# SCH___2025-09-30.net
KiCad netlist of a schematic drawn in EasyEDA
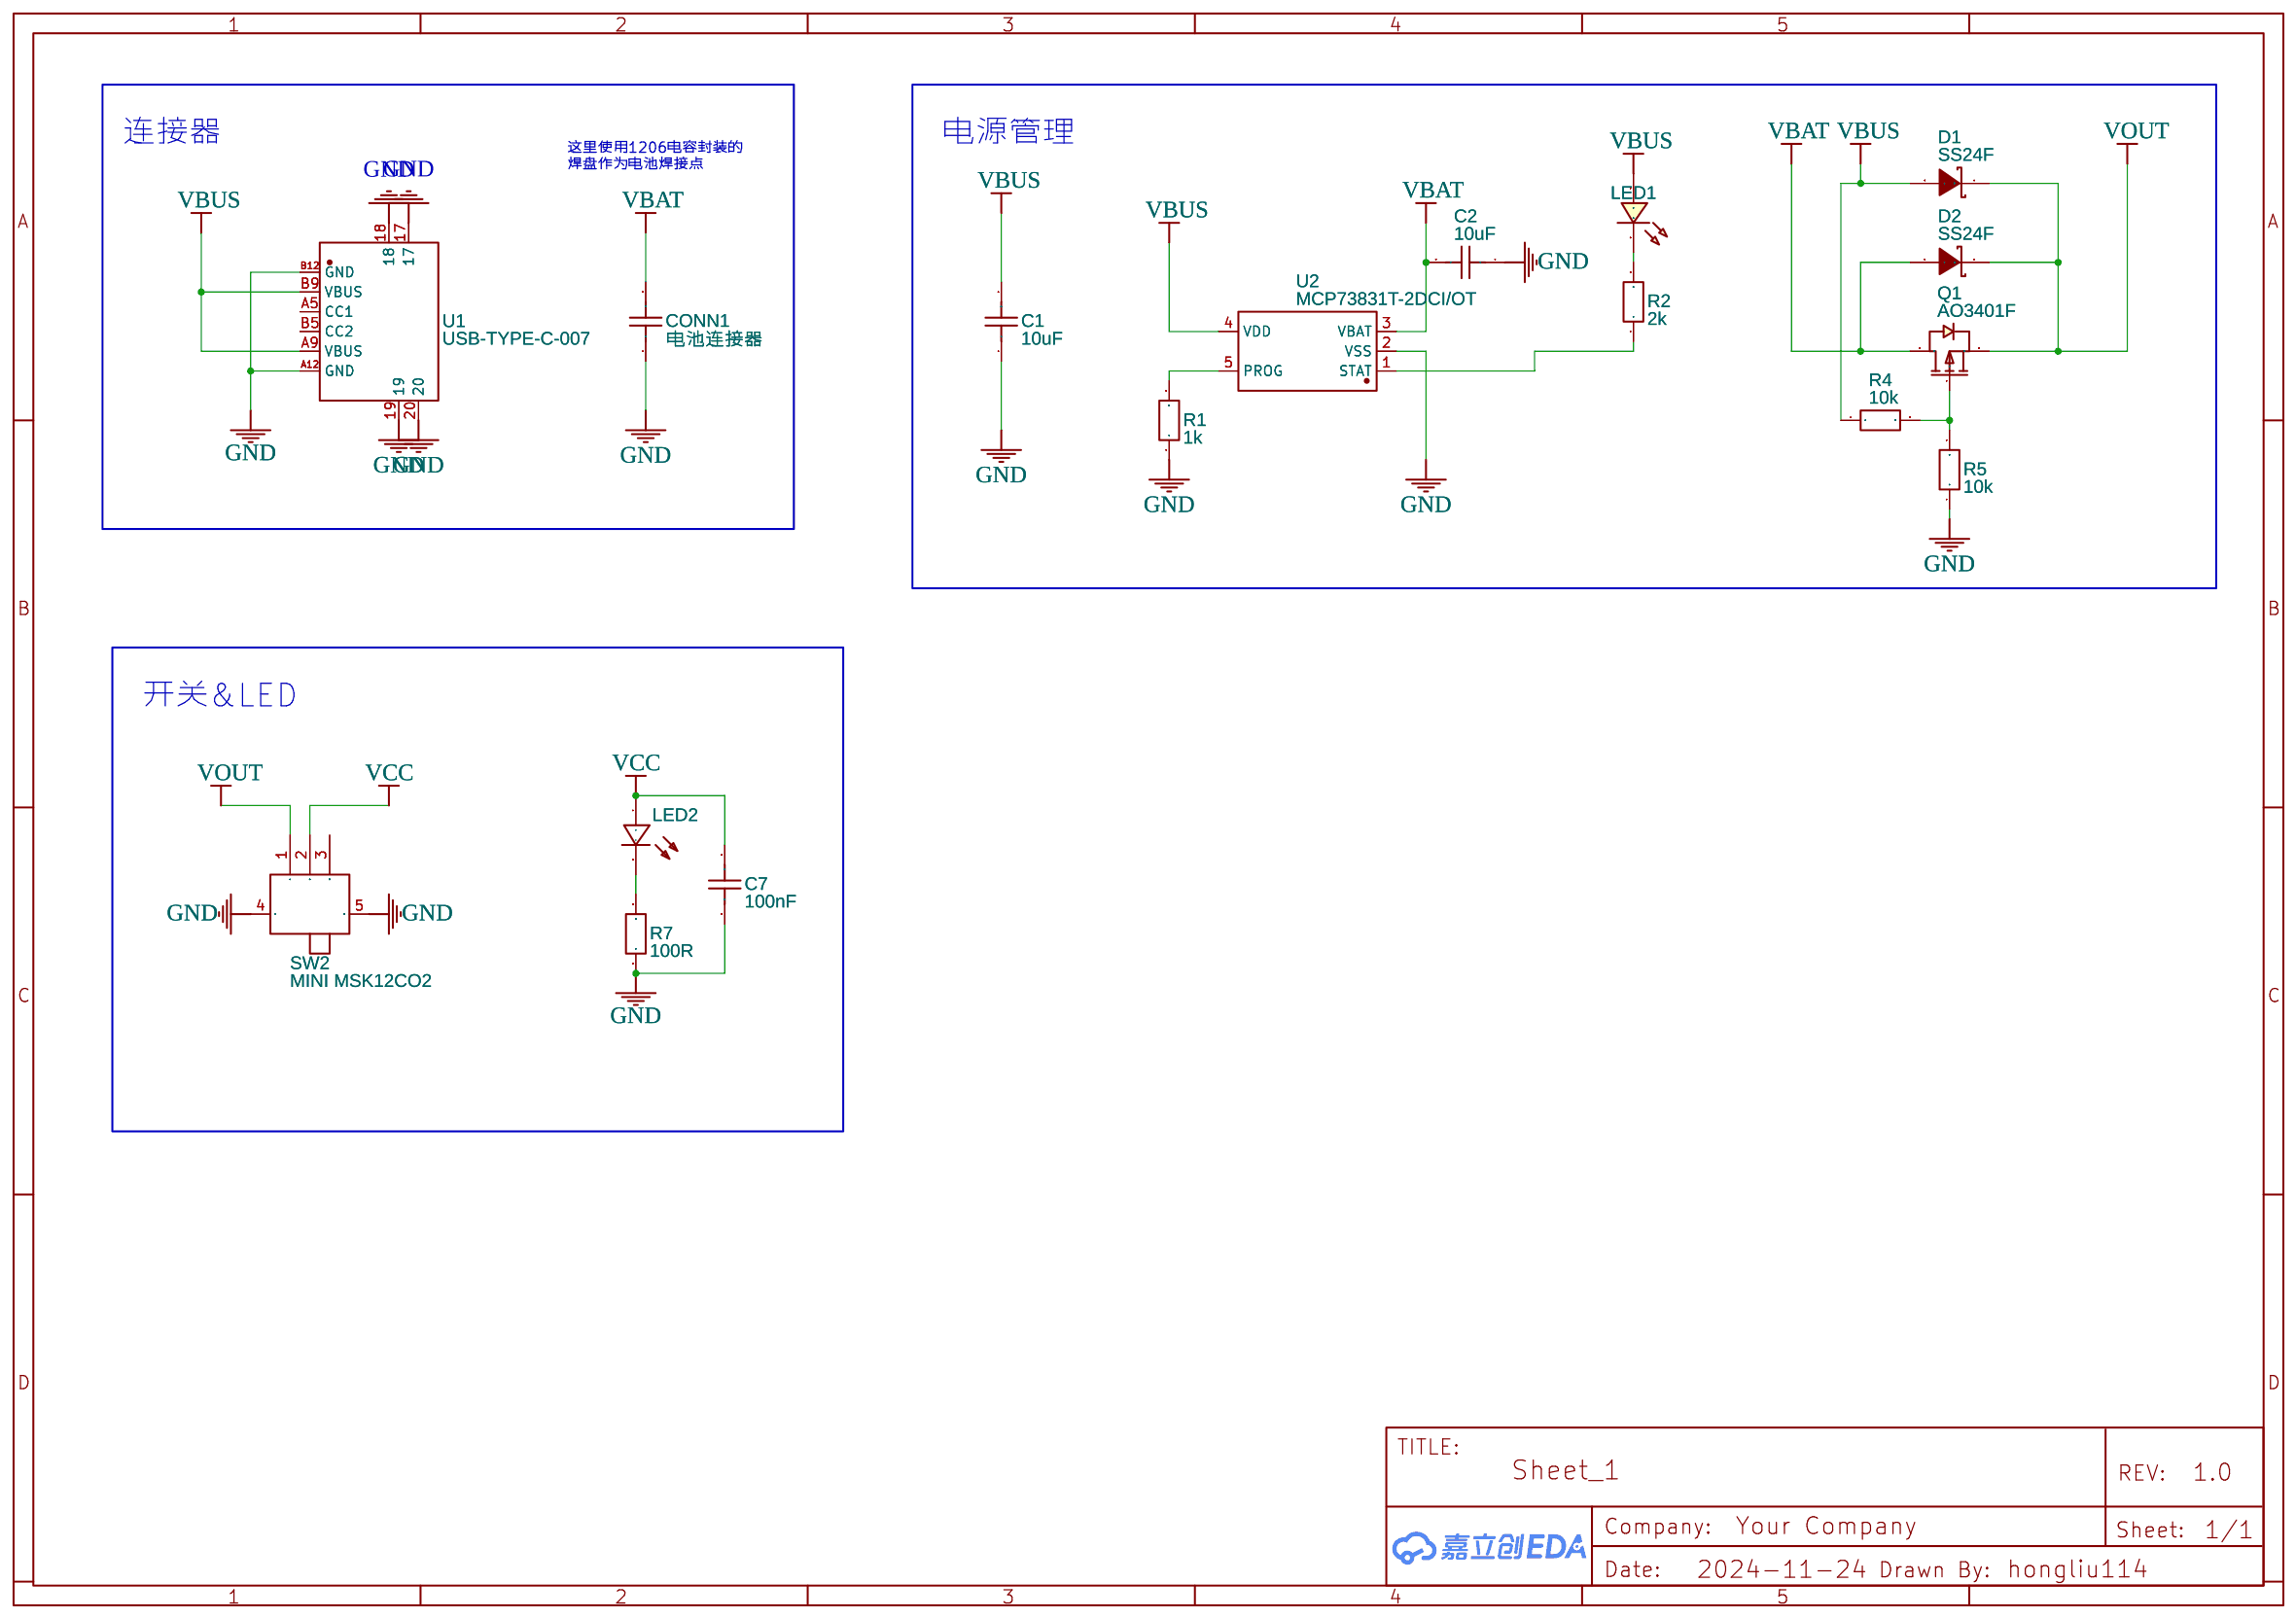
[diagram p0: schematic sheet]

(export (version "E")
  (design (tool "Eeschema 10.0.6"))
  (components
    (comp (ref "C1") (value "10uF") (libsource (lib "") (part "C_0603_US_1")))
    (comp (ref "C2") (value "10uF") (libsource (lib "") (part "C_0603_US")))
    (comp (ref "C7") (value "100nF") (libsource (lib "") (part "C_0603_US_2")))
    (comp (ref "CONN1")
      (value "电池连接器")
      (fields
        (field (name "Manufacturer Part") "C1206X119D8HACAUTO")
        (field (name "Manufacturer") "KEMET(基美)")
      )
      (libsource (lib "") (part "C1206X119D8HACAUTO"))
    )
    (comp (ref "D1")
      (value "SS24F")
      (fields (field (name "Manufacturer") "晶导微电子"))
      (libsource (lib "") (part "SS24F"))
    )
    (comp (ref "D2")
      (value "SS24F")
      (fields (field (name "Manufacturer") "晶导微电子"))
      (libsource (lib "") (part "SS24F"))
    )
    (comp (ref "LED1")
      (value "LED-0603_G")
      (fields
        (field (name "Manufacturer Part") "19-217/R6C-AL1M2VY/3T")
        (field (name "Manufacturer") "EVERLIGHT(台湾亿光)")
      )
      (libsource (lib "") (part "LED-0603_R"))
    )
    (comp (ref "LED2") (value "LED陶瓷灯丝(26MM)") (libsource (lib "") (part "LED陶瓷灯丝(26MM)")))
    (comp (ref "Q1")
      (value "AO3401F")
      (fields (field (name "Manufacturer") "BORN(伯恩半导体)"))
      (libsource (lib "") (part "AO3401F"))
    )
    (comp (ref "R1") (value "1k") (libsource (lib "") (part "R_0603_EU_1")))
    (comp (ref "R2") (value "2k") (libsource (lib "") (part "R_0603_EU_1")))
    (comp (ref "R4") (value "10k") (libsource (lib "") (part "R_0603_EU")))
    (comp (ref "R5") (value "10k") (libsource (lib "") (part "R_0603_EU_1")))
    (comp (ref "R7") (value "100R") (libsource (lib "") (part "R_0603_EU_1")))
    (comp (ref "SW2")
      (value "MINI MSK12CO2")
      (fields (field (name "Manufacturer") "SHOU HAN(首韩)"))
      (libsource (lib "") (part "MINI MSK12CO2"))
    )
    (comp (ref "U1")
      (value "USB-TYPE-C-007")
      (fields (field (name "Manufacturer") "DEALON(德艺隆)"))
      (libsource (lib "") (part "USB-TYPE-C-007"))
    )
    (comp (ref "U2")
      (value "MCP73831T-2DCI/OT")
      (fields (field (name "Manufacturer") "MICROCHIP(美国微芯)"))
      (libsource (lib "") (part "MCP73831T-2DCI/OT"))
    )
  )
  (nets
    (net (code "1") (name "GND") (class "Default")
      (node (ref "C1") (pin "1") (pinfunction "1_1") (pintype "unspecified"))
      (node (ref "C2") (pin "1") (pinfunction "1_1") (pintype "unspecified"))
      (node (ref "C7") (pin "2") (pinfunction "2_2") (pintype "unspecified"))
      (node (ref "CONN1") (pin "1") (pinfunction "1_1") (pintype "unspecified"))
      (node (ref "R1") (pin "1") (pinfunction "1_1") (pintype "unspecified"))
      (node (ref "R5") (pin "1") (pinfunction "1_1") (pintype "unspecified"))
      (node (ref "R7") (pin "1") (pinfunction "1_1") (pintype "unspecified"))
      (node (ref "SW2") (pin "4") (pinfunction "4_4") (pintype "unspecified"))
      (node (ref "SW2") (pin "5") (pinfunction "5_5") (pintype "unspecified"))
      (node (ref "U1") (pin "17") (pinfunction "17_17") (pintype "unspecified"))
      (node (ref "U1") (pin "18") (pinfunction "18_18") (pintype "unspecified"))
      (node (ref "U1") (pin "19") (pinfunction "19_19") (pintype "unspecified"))
      (node (ref "U1") (pin "20") (pinfunction "20_20") (pintype "unspecified"))
      (node (ref "U1") (pin "A12") (pinfunction "GND_A12") (pintype "unspecified"))
      (node (ref "U1") (pin "B12") (pinfunction "GND_B12") (pintype "unspecified"))
      (node (ref "U2") (pin "2") (pinfunction "VSS_2") (pintype "unspecified"))
    )
    (net (code "2") (name "Net-(LED1-Pad2)") (class "Default")
      (node (ref "LED1") (pin "2") (pinfunction "2_2") (pintype "unspecified"))
      (node (ref "R2") (pin "2") (pinfunction "2_2") (pintype "unspecified"))
    )
    (net (code "3") (name "Net-(LED2--)") (class "Default")
      (node (ref "LED2") (pin "2") (pinfunction "-_2") (pintype "unspecified"))
      (node (ref "R7") (pin "2") (pinfunction "2_2") (pintype "unspecified"))
    )
    (net (code "4") (name "Net-(Q1-G)") (class "Default")
      (node (ref "Q1") (pin "1") (pinfunction "G_1") (pintype "unspecified"))
      (node (ref "R4") (pin "2") (pinfunction "2_2") (pintype "unspecified"))
      (node (ref "R5") (pin "2") (pinfunction "2_2") (pintype "unspecified"))
    )
    (net (code "5") (name "Net-(U2-PROG)") (class "Default")
      (node (ref "R1") (pin "2") (pinfunction "2_2") (pintype "unspecified"))
      (node (ref "U2") (pin "5") (pinfunction "PROG_5") (pintype "unspecified"))
    )
    (net (code "6") (name "Net-(U2-STAT)") (class "Default")
      (node (ref "R2") (pin "1") (pinfunction "1_1") (pintype "unspecified"))
      (node (ref "U2") (pin "1") (pinfunction "STAT_1") (pintype "unspecified"))
    )
    (net (code "7") (name "VBAT") (class "Default")
      (node (ref "C2") (pin "2") (pinfunction "2_2") (pintype "unspecified"))
      (node (ref "CONN1") (pin "2") (pinfunction "2_2") (pintype "unspecified"))
      (node (ref "D2") (pin "2") (pinfunction "A_2") (pintype "unspecified"))
      (node (ref "Q1") (pin "3") (pinfunction "D_3") (pintype "unspecified"))
      (node (ref "U2") (pin "3") (pinfunction "VBAT_3") (pintype "unspecified"))
    )
    (net (code "8") (name "VBUS") (class "Default")
      (node (ref "C1") (pin "2") (pinfunction "2_2") (pintype "unspecified"))
      (node (ref "D1") (pin "2") (pinfunction "A_2") (pintype "unspecified"))
      (node (ref "LED1") (pin "1") (pinfunction "1_1") (pintype "unspecified"))
      (node (ref "R4") (pin "1") (pinfunction "1_1") (pintype "unspecified"))
      (node (ref "U1") (pin "A9") (pinfunction "VBUS_A9") (pintype "unspecified"))
      (node (ref "U1") (pin "B9") (pinfunction "VBUS_B9") (pintype "unspecified"))
      (node (ref "U2") (pin "4") (pinfunction "VDD_4") (pintype "unspecified"))
    )
    (net (code "9") (name "VCC") (class "Default")
      (node (ref "C7") (pin "1") (pinfunction "1_1") (pintype "unspecified"))
      (node (ref "LED2") (pin "1") (pinfunction "+_1") (pintype "unspecified"))
      (node (ref "SW2") (pin "2") (pinfunction "2_2") (pintype "unspecified"))
    )
    (net (code "10") (name "VOUT") (class "Default")
      (node (ref "D1") (pin "1") (pinfunction "C_1") (pintype "unspecified"))
      (node (ref "D2") (pin "1") (pinfunction "C_1") (pintype "unspecified"))
      (node (ref "Q1") (pin "2") (pinfunction "S_2") (pintype "unspecified"))
      (node (ref "SW2") (pin "1") (pinfunction "1_1") (pintype "unspecified"))
    )
    (net (code "11") (name "unconnected-(SW2-Pad3)") (class "Default")
      (node (ref "SW2") (pin "3") (pinfunction "3_3") (pintype "unspecified"))
    )
    (net (code "12") (name "unconnected-(U1-CC1-PadA5)") (class "Default")
      (node (ref "U1") (pin "A5") (pinfunction "CC1_A5") (pintype "unspecified"))
    )
    (net (code "13") (name "unconnected-(U1-CC2-PadB5)") (class "Default")
      (node (ref "U1") (pin "B5") (pinfunction "CC2_B5") (pintype "unspecified"))
    )
  )
)
